# Schematic.net
KiCad netlist of a schematic drawn in EasyEDA
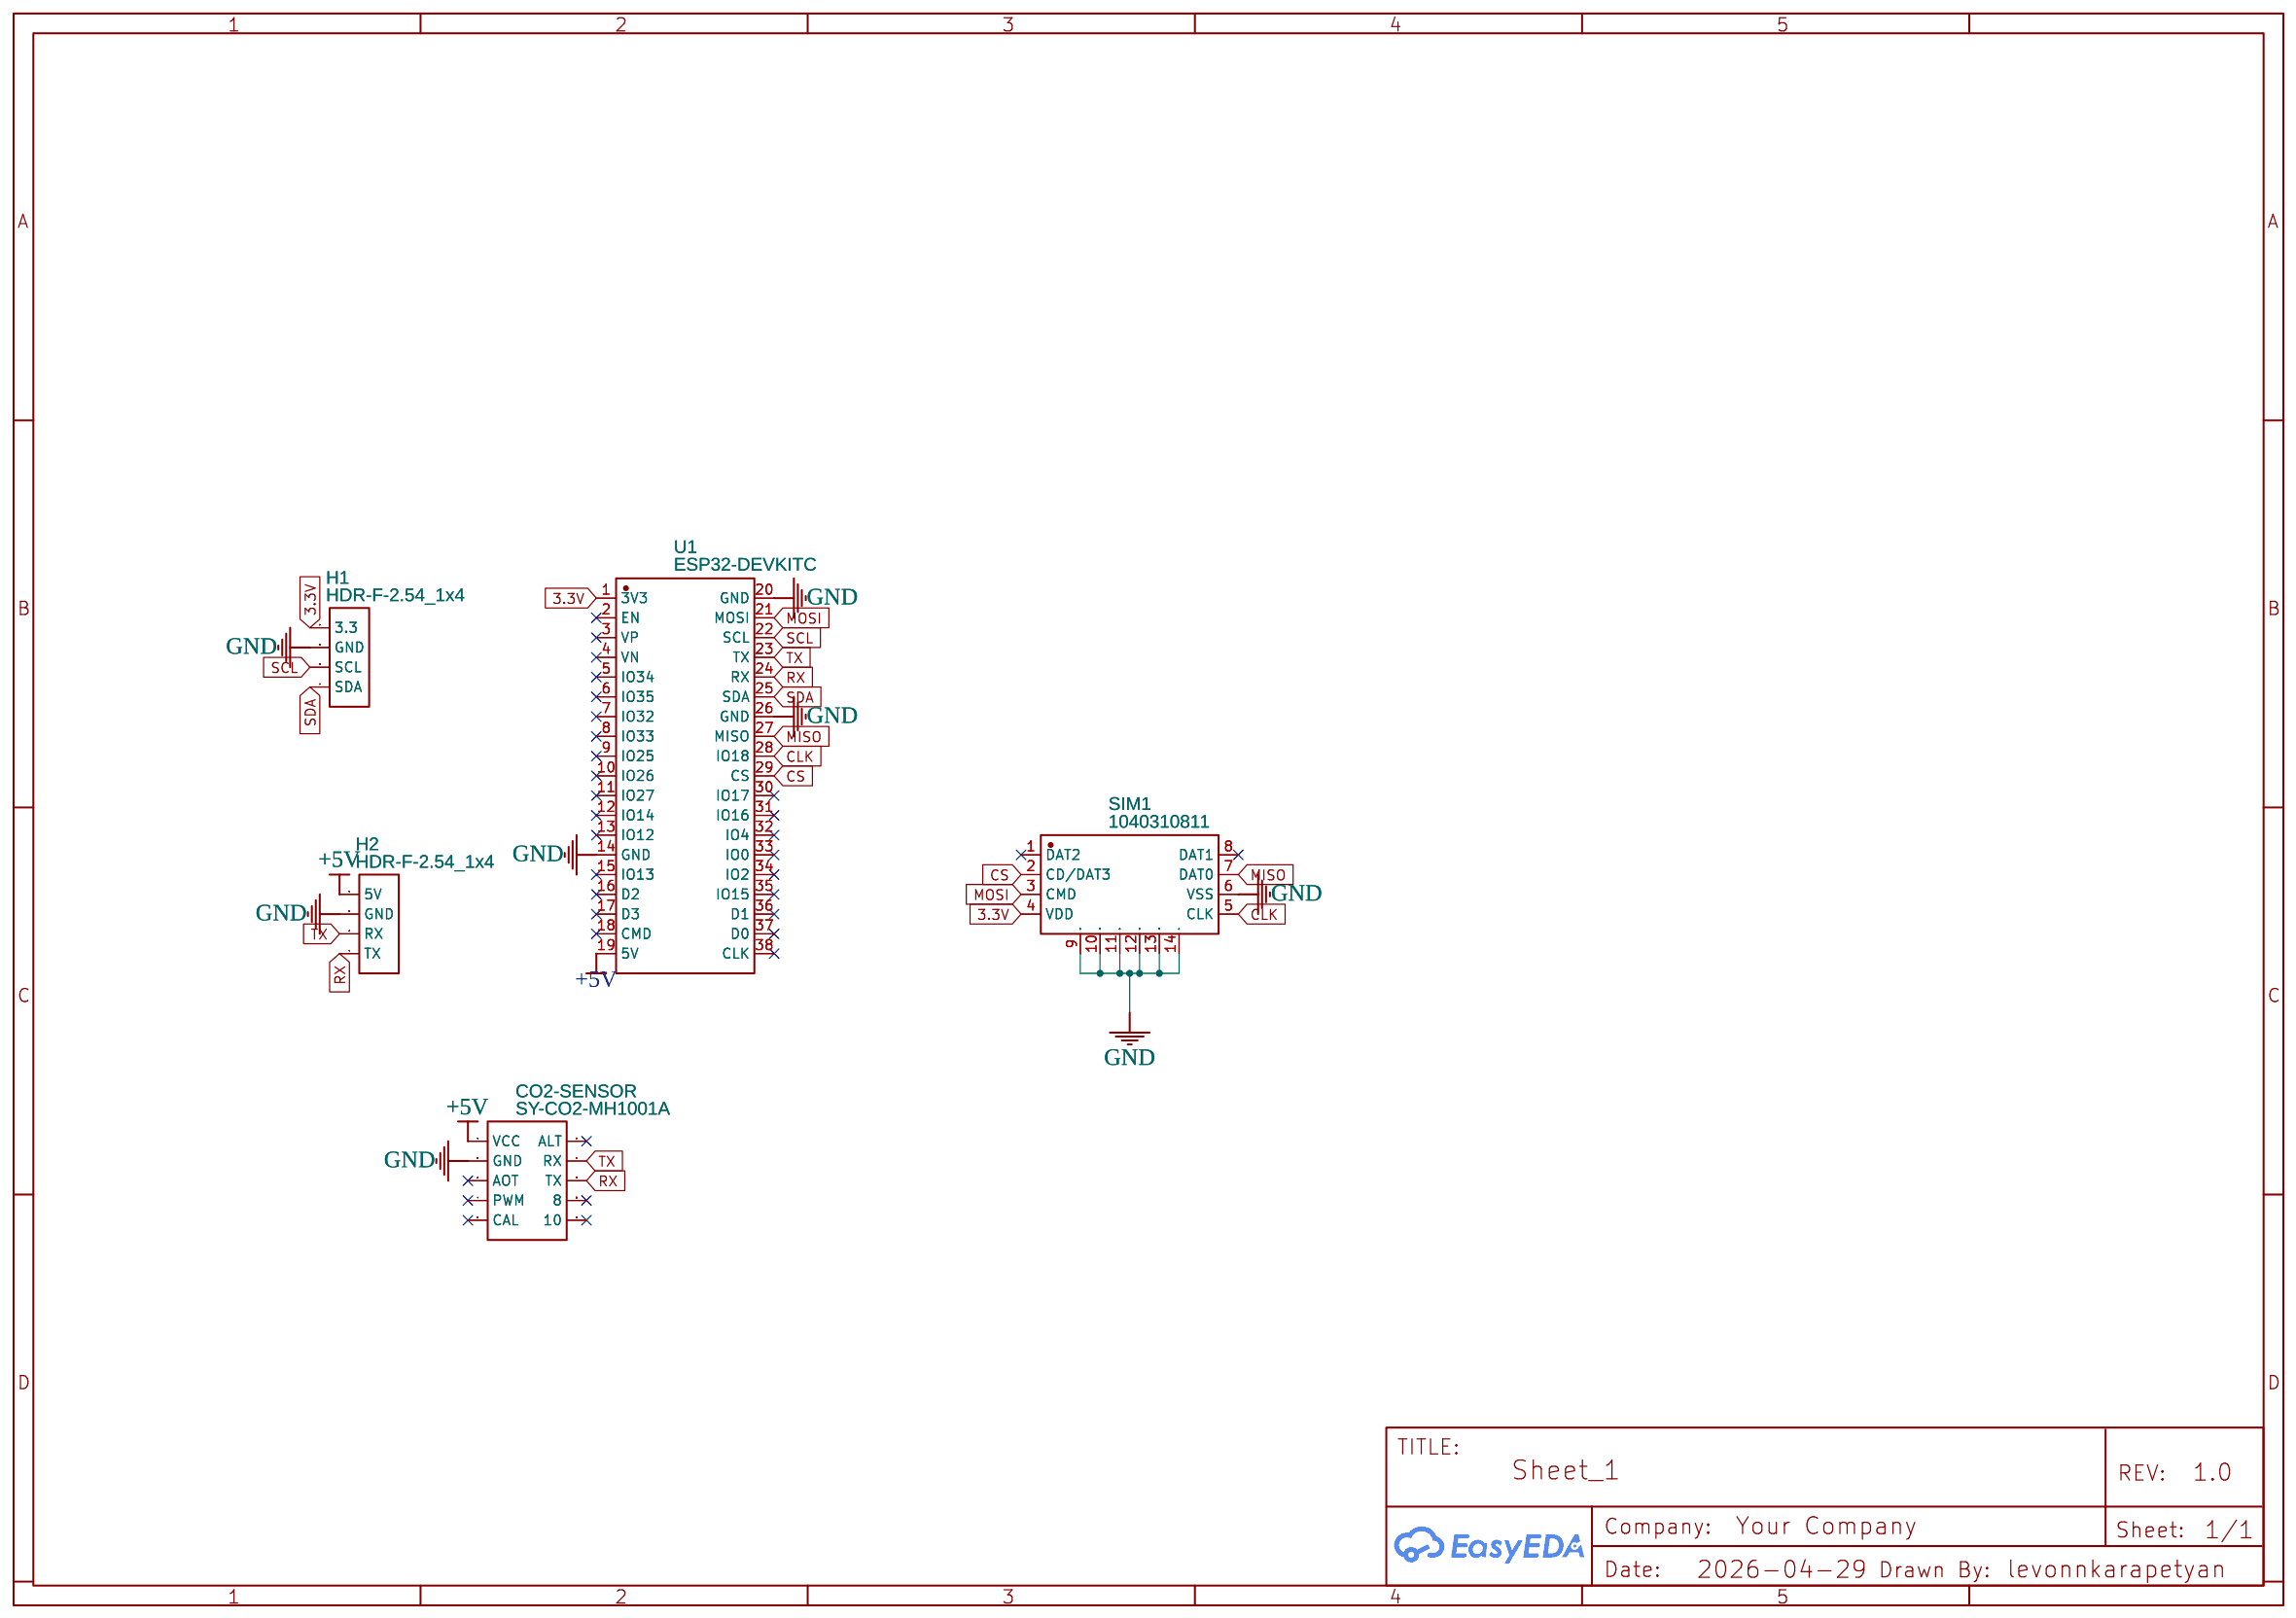
[diagram p0: schematic sheet]

(export (version "E")
  (design (tool "Eeschema 10.0.6"))
  (components
    (comp (ref "CO2-SENSOR") (value "SY-CO2-MH1001A") (libsource (lib "") (part "HDR-F-2.54_2x5")))
    (comp (ref "H1") (value "HDR-F-2.54_1x4") (libsource (lib "") (part "HDR-F-2.54_1x4")))
    (comp (ref "H2") (value "HDR-F-2.54_1x4") (libsource (lib "") (part "HDR-F-2.54_1x4_1")))
    (comp (ref "SIM1")
      (value "1040310811")
      (fields (field (name "Manufacturer") "MOLEX"))
      (libsource (lib "") (part "1040310811"))
    )
    (comp (ref "U1")
      (value "ESP32-DEVKITC")
      (fields
        (field (name "Manufacturer Part") "ESP32-DevKitC")
        (field (name "Manufacturer") "ESPRESSIF(乐鑫)")
      )
      (libsource (lib "") (part "ESP32-DEVKITC"))
    )
  )
  (nets
    (net (code "1") (name "+5V") (class "Default")
      (node (ref "CO2-SENSOR") (pin "1") (pinfunction "VCC_1") (pintype "unspecified"))
      (node (ref "H2") (pin "1") (pinfunction "5V_1") (pintype "unspecified"))
      (node (ref "U1") (pin "19") (pinfunction "5V_19") (pintype "unspecified"))
    )
    (net (code "2") (name "3.3V") (class "Default")
      (node (ref "H1") (pin "1") (pinfunction "3.3_1") (pintype "unspecified"))
      (node (ref "SIM1") (pin "4") (pinfunction "VDD_4") (pintype "unspecified"))
      (node (ref "U1") (pin "1") (pinfunction "3V3_1") (pintype "unspecified"))
    )
    (net (code "3") (name "CLK") (class "Default")
      (node (ref "SIM1") (pin "5") (pinfunction "CLK_5") (pintype "unspecified"))
      (node (ref "U1") (pin "28") (pinfunction "IO18_28") (pintype "unspecified"))
    )
    (net (code "4") (name "CS") (class "Default")
      (node (ref "SIM1") (pin "2") (pinfunction "CD/DAT3_2") (pintype "unspecified"))
      (node (ref "U1") (pin "29") (pinfunction "CS_29") (pintype "unspecified"))
    )
    (net (code "5") (name "GND") (class "Default")
      (node (ref "CO2-SENSOR") (pin "3") (pinfunction "GND_3") (pintype "unspecified"))
      (node (ref "H1") (pin "2") (pinfunction "GND_2") (pintype "unspecified"))
      (node (ref "H2") (pin "2") (pinfunction "GND_2") (pintype "unspecified"))
      (node (ref "SIM1") (pin "10") (pinfunction "10_10") (pintype "unspecified"))
      (node (ref "SIM1") (pin "11") (pinfunction "11_11") (pintype "unspecified"))
      (node (ref "SIM1") (pin "12") (pinfunction "12_12") (pintype "unspecified"))
      (node (ref "SIM1") (pin "13") (pinfunction "13_13") (pintype "unspecified"))
      (node (ref "SIM1") (pin "14") (pinfunction "14_14") (pintype "unspecified"))
      (node (ref "SIM1") (pin "6") (pinfunction "VSS_6") (pintype "unspecified"))
      (node (ref "SIM1") (pin "9") (pinfunction "9_9") (pintype "unspecified"))
      (node (ref "U1") (pin "14") (pinfunction "GND_14") (pintype "unspecified"))
      (node (ref "U1") (pin "20") (pinfunction "GND_20") (pintype "unspecified"))
      (node (ref "U1") (pin "26") (pinfunction "GND_26") (pintype "unspecified"))
    )
    (net (code "6") (name "MISO") (class "Default")
      (node (ref "SIM1") (pin "7") (pinfunction "DAT0_7") (pintype "unspecified"))
      (node (ref "U1") (pin "27") (pinfunction "MISO_27") (pintype "unspecified"))
    )
    (net (code "7") (name "MOSI") (class "Default")
      (node (ref "SIM1") (pin "3") (pinfunction "CMD_3") (pintype "unspecified"))
      (node (ref "U1") (pin "21") (pinfunction "MOSI_21") (pintype "unspecified"))
    )
    (net (code "8") (name "RX") (class "Default")
      (node (ref "CO2-SENSOR") (pin "6") (pinfunction "TX_6") (pintype "unspecified"))
      (node (ref "H2") (pin "4") (pinfunction "TX_4") (pintype "unspecified"))
      (node (ref "U1") (pin "24") (pinfunction "RX_24") (pintype "unspecified"))
    )
    (net (code "9") (name "SCL") (class "Default")
      (node (ref "H1") (pin "3") (pinfunction "SCL_3") (pintype "unspecified"))
      (node (ref "U1") (pin "22") (pinfunction "SCL_22") (pintype "unspecified"))
    )
    (net (code "10") (name "SDA") (class "Default")
      (node (ref "H1") (pin "4") (pinfunction "SDA_4") (pintype "unspecified"))
      (node (ref "U1") (pin "25") (pinfunction "SDA_25") (pintype "unspecified"))
    )
    (net (code "11") (name "TX") (class "Default")
      (node (ref "CO2-SENSOR") (pin "4") (pinfunction "RX_4") (pintype "unspecified"))
      (node (ref "H2") (pin "3") (pinfunction "RX_3") (pintype "unspecified"))
      (node (ref "U1") (pin "23") (pinfunction "TX_23") (pintype "unspecified"))
    )
    (net (code "12") (name "unconnected-(CO2-SENSOR-ALT-Pad2)") (class "Default")
      (node (ref "CO2-SENSOR") (pin "2") (pinfunction "ALT_2") (pintype "unspecified+no_connect"))
    )
    (net (code "13") (name "unconnected-(CO2-SENSOR-AOT-Pad5)") (class "Default")
      (node (ref "CO2-SENSOR") (pin "5") (pinfunction "AOT_5") (pintype "unspecified+no_connect"))
    )
    (net (code "14") (name "unconnected-(CO2-SENSOR-CAL-Pad9)") (class "Default")
      (node (ref "CO2-SENSOR") (pin "9") (pinfunction "CAL_9") (pintype "unspecified+no_connect"))
    )
    (net (code "15") (name "unconnected-(CO2-SENSOR-PWM-Pad7)") (class "Default")
      (node (ref "CO2-SENSOR") (pin "7") (pinfunction "PWM_7") (pintype "unspecified+no_connect"))
    )
    (net (code "16") (name "unconnected-(CO2-SENSOR-Pad8)") (class "Default")
      (node (ref "CO2-SENSOR") (pin "8") (pinfunction "8_8") (pintype "unspecified+no_connect"))
    )
    (net (code "17") (name "unconnected-(CO2-SENSOR-Pad10)") (class "Default")
      (node (ref "CO2-SENSOR") (pin "10") (pinfunction "10_10") (pintype "unspecified+no_connect"))
    )
    (net (code "18") (name "unconnected-(SIM1-DAT1-Pad8)") (class "Default")
      (node (ref "SIM1") (pin "8") (pinfunction "DAT1_8") (pintype "unspecified+no_connect"))
    )
    (net (code "19") (name "unconnected-(SIM1-DAT2-Pad1)") (class "Default")
      (node (ref "SIM1") (pin "1") (pinfunction "DAT2_1") (pintype "unspecified+no_connect"))
    )
    (net (code "20") (name "unconnected-(U1-CLK-Pad38)") (class "Default")
      (node (ref "U1") (pin "38") (pinfunction "CLK_38") (pintype "unspecified+no_connect"))
    )
    (net (code "21") (name "unconnected-(U1-CMD-Pad18)") (class "Default")
      (node (ref "U1") (pin "18") (pinfunction "CMD_18") (pintype "unspecified+no_connect"))
    )
    (net (code "22") (name "unconnected-(U1-D0-Pad37)") (class "Default")
      (node (ref "U1") (pin "37") (pinfunction "D0_37") (pintype "unspecified+no_connect"))
    )
    (net (code "23") (name "unconnected-(U1-D1-Pad36)") (class "Default")
      (node (ref "U1") (pin "36") (pinfunction "D1_36") (pintype "unspecified+no_connect"))
    )
    (net (code "24") (name "unconnected-(U1-D2-Pad16)") (class "Default")
      (node (ref "U1") (pin "16") (pinfunction "D2_16") (pintype "unspecified+no_connect"))
    )
    (net (code "25") (name "unconnected-(U1-D3-Pad17)") (class "Default")
      (node (ref "U1") (pin "17") (pinfunction "D3_17") (pintype "unspecified+no_connect"))
    )
    (net (code "26") (name "unconnected-(U1-EN-Pad2)") (class "Default")
      (node (ref "U1") (pin "2") (pinfunction "EN_2") (pintype "unspecified+no_connect"))
    )
    (net (code "27") (name "unconnected-(U1-IO0-Pad33)") (class "Default")
      (node (ref "U1") (pin "33") (pinfunction "IO0_33") (pintype "unspecified+no_connect"))
    )
    (net (code "28") (name "unconnected-(U1-IO2-Pad34)") (class "Default")
      (node (ref "U1") (pin "34") (pinfunction "IO2_34") (pintype "unspecified+no_connect"))
    )
    (net (code "29") (name "unconnected-(U1-IO4-Pad32)") (class "Default")
      (node (ref "U1") (pin "32") (pinfunction "IO4_32") (pintype "unspecified+no_connect"))
    )
    (net (code "30") (name "unconnected-(U1-IO12-Pad13)") (class "Default")
      (node (ref "U1") (pin "13") (pinfunction "IO12_13") (pintype "unspecified+no_connect"))
    )
    (net (code "31") (name "unconnected-(U1-IO13-Pad15)") (class "Default")
      (node (ref "U1") (pin "15") (pinfunction "IO13_15") (pintype "unspecified+no_connect"))
    )
    (net (code "32") (name "unconnected-(U1-IO14-Pad12)") (class "Default")
      (node (ref "U1") (pin "12") (pinfunction "IO14_12") (pintype "unspecified+no_connect"))
    )
    (net (code "33") (name "unconnected-(U1-IO15-Pad35)") (class "Default")
      (node (ref "U1") (pin "35") (pinfunction "IO15_35") (pintype "unspecified+no_connect"))
    )
    (net (code "34") (name "unconnected-(U1-IO16-Pad31)") (class "Default")
      (node (ref "U1") (pin "31") (pinfunction "IO16_31") (pintype "unspecified+no_connect"))
    )
    (net (code "35") (name "unconnected-(U1-IO17-Pad30)") (class "Default")
      (node (ref "U1") (pin "30") (pinfunction "IO17_30") (pintype "unspecified+no_connect"))
    )
    (net (code "36") (name "unconnected-(U1-IO25-Pad9)") (class "Default")
      (node (ref "U1") (pin "9") (pinfunction "IO25_9") (pintype "unspecified+no_connect"))
    )
    (net (code "37") (name "unconnected-(U1-IO26-Pad10)") (class "Default")
      (node (ref "U1") (pin "10") (pinfunction "IO26_10") (pintype "unspecified+no_connect"))
    )
    (net (code "38") (name "unconnected-(U1-IO27-Pad11)") (class "Default")
      (node (ref "U1") (pin "11") (pinfunction "IO27_11") (pintype "unspecified+no_connect"))
    )
    (net (code "39") (name "unconnected-(U1-IO32-Pad7)") (class "Default")
      (node (ref "U1") (pin "7") (pinfunction "IO32_7") (pintype "unspecified+no_connect"))
    )
    (net (code "40") (name "unconnected-(U1-IO33-Pad8)") (class "Default")
      (node (ref "U1") (pin "8") (pinfunction "IO33_8") (pintype "unspecified+no_connect"))
    )
    (net (code "41") (name "unconnected-(U1-IO34-Pad5)") (class "Default")
      (node (ref "U1") (pin "5") (pinfunction "IO34_5") (pintype "unspecified+no_connect"))
    )
    (net (code "42") (name "unconnected-(U1-IO35-Pad6)") (class "Default")
      (node (ref "U1") (pin "6") (pinfunction "IO35_6") (pintype "unspecified+no_connect"))
    )
    (net (code "43") (name "unconnected-(U1-VN-Pad4)") (class "Default")
      (node (ref "U1") (pin "4") (pinfunction "VN_4") (pintype "unspecified+no_connect"))
    )
    (net (code "44") (name "unconnected-(U1-VP-Pad3)") (class "Default")
      (node (ref "U1") (pin "3") (pinfunction "VP_3") (pintype "unspecified+no_connect"))
    )
  )
)
